# Addon-mapleCUx_OneWire-RS485-003.net
KiCad netlist of a schematic drawn in EAGLE
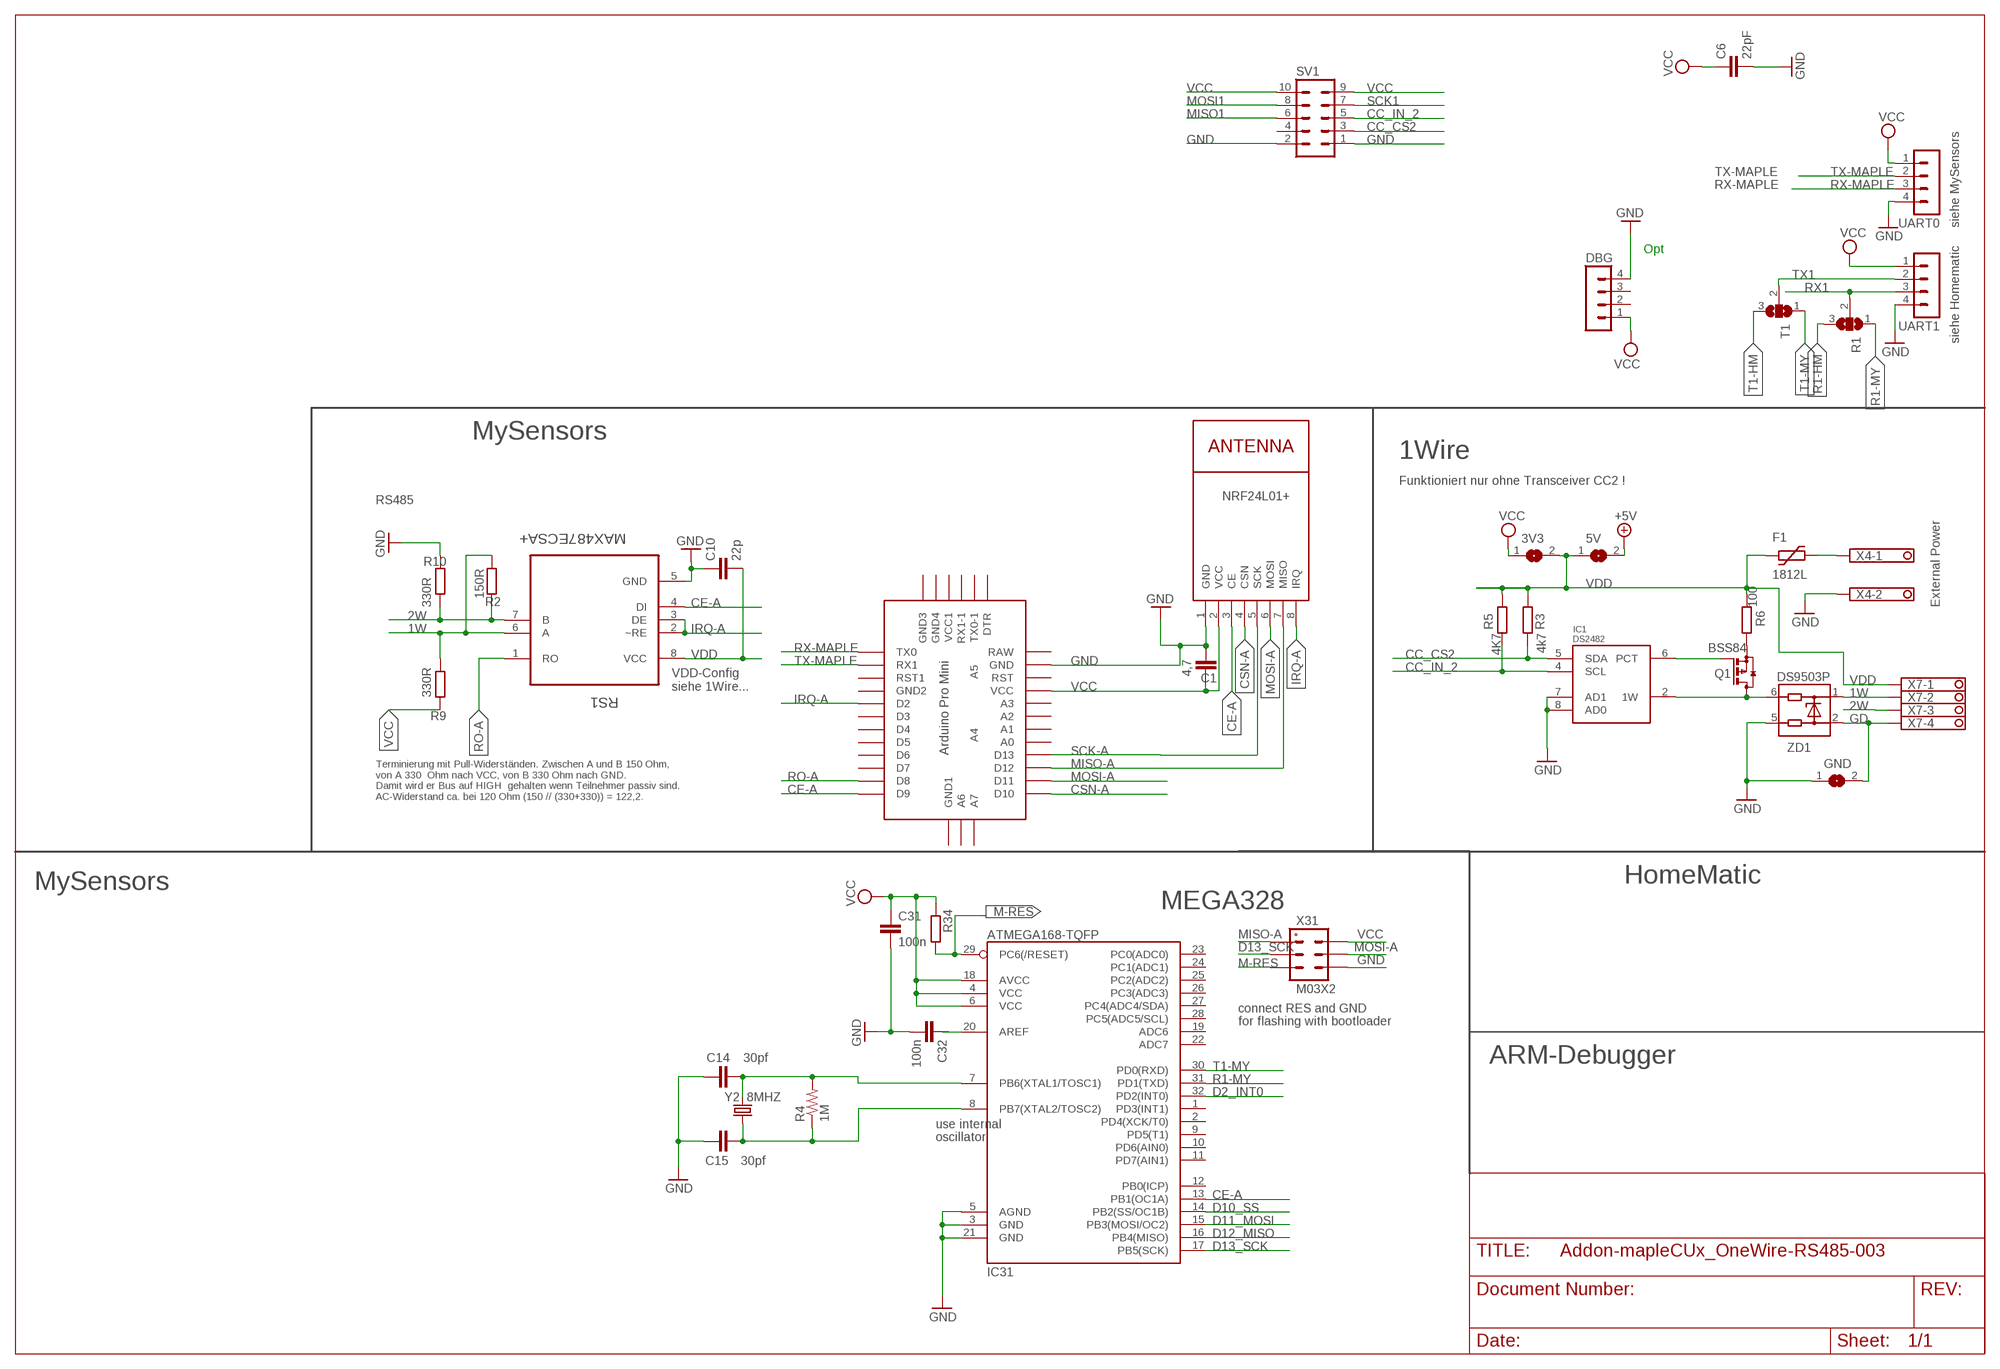
[diagram p0: schematic, sheet 1]

(export (version "E")
  (design (tool "Eeschema 10.0.6"))
  (components
    (comp (ref "3V3") (value "SJ") (footprint "eagle-import:SJ") (libsource (lib "eagle-import") (part "SJ")))
    (comp (ref "5V") (value "SJ") (footprint "eagle-import:SJ") (libsource (lib "eagle-import") (part "SJ")))
    (comp (ref "C1")
      (value "4,7")
      (footprint "eagle-import:C1210")
      (libsource (lib "eagle-import") (part "C-EUC1210"))
    )
    (comp (ref "C6")
      (value "22pF")
      (footprint "eagle-import:C0805")
      (libsource (lib "eagle-import") (part "C-EUC0805"))
    )
    (comp (ref "C10")
      (value "22p")
      (footprint "eagle-import:C0805")
      (libsource (lib "eagle-import") (part "C-EUC0805"))
    )
    (comp (ref "C14")
      (value "30pf")
      (footprint "eagle-import:0805")
      (libsource (lib "eagle-import") (part "CAP0805"))
    )
    (comp (ref "C15")
      (value "30pf")
      (footprint "eagle-import:0805")
      (libsource (lib "eagle-import") (part "CAP0805"))
    )
    (comp (ref "C31")
      (value "100n")
      (footprint "eagle-import:C0805")
      (libsource (lib "eagle-import") (part "C-EUC0805"))
    )
    (comp (ref "C32")
      (value "100n")
      (footprint "eagle-import:C0805")
      (libsource (lib "eagle-import") (part "C-EUC0805"))
    )
    (comp (ref "DBG")
      (value "MA04-1")
      (footprint "eagle-import:MA04-1")
      (libsource (lib "eagle-import") (part "MA04-1"))
    )
    (comp (ref "F1")
      (value "1812L")
      (footprint "eagle-import:1812L")
      (libsource (lib "eagle-import") (part "1812L"))
    )
    (comp (ref "GND") (value "SJ") (footprint "eagle-import:SJ") (libsource (lib "eagle-import") (part "SJ")))
    (comp (ref "IC1")
      (value "DS2482")
      (footprint "eagle-import:SO08")
      (libsource (lib "eagle-import") (part "DS2482-100S"))
    )
    (comp (ref "IC31")
      (value "ATMEGA168-TQFP")
      (footprint "eagle-import:TQFP32-08")
      (libsource (lib "eagle-import") (part "ATMEGA168-TQFP"))
    )
    (comp (ref "NRF24L01+")
      (value "NRF24L01+")
      (footprint "eagle-import:WIRELESS-NRF24L01")
      (libsource (lib "eagle-import") (part "WIRELESS-NRF24L01"))
    )
    (comp (ref "Q1")
      (value "BSS84")
      (footprint "eagle-import:SOT23")
      (libsource (lib "eagle-import") (part "BSS84"))
    )
    (comp (ref "R1")
      (value "SJ2W")
      (footprint "eagle-import:SJ_2")
      (libsource (lib "eagle-import") (part "SJ2W"))
    )
    (comp (ref "R2")
      (value "150R")
      (footprint "eagle-import:R0805")
      (libsource (lib "eagle-import") (part "R-EU_R0805"))
    )
    (comp (ref "R3")
      (value "4k7")
      (footprint "eagle-import:R0805")
      (libsource (lib "eagle-import") (part "R-EU_R0805"))
    )
    (comp (ref "R4")
      (value "1M")
      (footprint "eagle-import:0805")
      (libsource (lib "eagle-import") (part "RESISTOR0805-RES"))
    )
    (comp (ref "R5")
      (value "4K7")
      (footprint "eagle-import:R0805")
      (libsource (lib "eagle-import") (part "R-EU_R0805"))
    )
    (comp (ref "R6")
      (value "100")
      (footprint "eagle-import:R0805")
      (libsource (lib "eagle-import") (part "R-EU_R0805"))
    )
    (comp (ref "R9")
      (value "330R")
      (footprint "eagle-import:R0805")
      (libsource (lib "eagle-import") (part "R-EU_R0805"))
    )
    (comp (ref "R10")
      (value "330R")
      (footprint "eagle-import:R0805")
      (libsource (lib "eagle-import") (part "R-EU_R0805"))
    )
    (comp (ref "R34")
      (value "R-EU_R0805")
      (footprint "eagle-import:R0805")
      (libsource (lib "eagle-import") (part "R-EU_R0805"))
    )
    (comp (ref "RS1")
      (value "MAX487ECSA+")
      (footprint "eagle-import:SOIC127P600X175-8N")
      (libsource (lib "eagle-import") (part "MAX487ECSA+"))
    )
    (comp (ref "SV1")
      (value "MA05-2")
      (footprint "eagle-import:MA05-2")
      (libsource (lib "eagle-import") (part "MA05-2"))
    )
    (comp (ref "T1")
      (value "SJ2W")
      (footprint "eagle-import:SJ_2")
      (libsource (lib "eagle-import") (part "SJ2W"))
    )
    (comp (ref "U$1")
      (value "ABK-PRO-MINI")
      (footprint "eagle-import:ABK-PRO-MINI")
      (libsource (lib "eagle-import") (part "ABK-PRO-MINI"))
    )
    (comp (ref "UART0")
      (value "MA04-1")
      (footprint "eagle-import:MA04-1")
      (libsource (lib "eagle-import") (part "MA04-1"))
    )
    (comp (ref "UART1")
      (value "MA04-1")
      (footprint "eagle-import:MA04-1")
      (libsource (lib "eagle-import") (part "MA04-1"))
    )
    (comp (ref "X4")
      (value "1751248")
      (footprint "eagle-import:1751248")
      (libsource (lib "eagle-import") (part "1751248"))
    )
    (comp (ref "X7")
      (value "1751264")
      (footprint "eagle-import:1751264")
      (libsource (lib "eagle-import") (part "1751264"))
    )
    (comp (ref "X31")
      (value "M03X2")
      (footprint "eagle-import:2X03-1.27MM_SMD")
      (libsource (lib "eagle-import") (part "M03X2"))
    )
    (comp (ref "Y2")
      (value "8MHZ")
      (footprint "eagle-import:CRYSTAL-TXC-7A")
      (libsource (lib "eagle-import") (part "CRYSTALTXC-7A"))
    )
    (comp (ref "ZD1")
      (value "DS9503P")
      (footprint "eagle-import:TSOC6")
      (libsource (lib "eagle-import") (part "DS9503P"))
    )
  )
  (nets
    (net (code "1") (name "+5V") (class "Default")
      (node (ref "5V") (pin "2") (pinfunction "2_2") (pintype "passive"))
    )
    (net (code "2") (name "/1W") (class "Default")
      (node (ref "R2") (pin "1") (pinfunction "1_1") (pintype "passive"))
      (node (ref "R9") (pin "2") (pinfunction "2_2") (pintype "passive"))
      (node (ref "RS1") (pin "6") (pinfunction "A_6") (pintype "bidirectional"))
      (node (ref "X7") (pin "2") (pinfunction "K_2") (pintype "passive"))
      (node (ref "ZD1") (pin "1") (pinfunction "P$1_1") (pintype "passive"))
    )
    (net (code "3") (name "/2W") (class "Default")
      (node (ref "R10") (pin "1") (pinfunction "1_1") (pintype "passive"))
      (node (ref "R2") (pin "2") (pinfunction "2_2") (pintype "passive"))
      (node (ref "RS1") (pin "7") (pinfunction "B_7") (pintype "bidirectional"))
      (node (ref "X7") (pin "3") (pinfunction "K_3") (pintype "passive"))
    )
    (net (code "4") (name "/CC_CS2") (class "Default")
      (node (ref "IC1") (pin "5") (pinfunction "SDA_5") (pintype "bidirectional"))
      (node (ref "R3") (pin "2") (pinfunction "2_2") (pintype "passive"))
      (node (ref "SV1") (pin "3") (pinfunction "3_3") (pintype "passive"))
    )
    (net (code "5") (name "/CC_IN_2") (class "Default")
      (node (ref "IC1") (pin "4") (pinfunction "SCL_4") (pintype "input"))
      (node (ref "R5") (pin "2") (pinfunction "2_2") (pintype "passive"))
      (node (ref "SV1") (pin "5") (pinfunction "5_5") (pintype "passive"))
    )
    (net (code "6") (name "/D2_INT0") (class "Default")
      (node (ref "IC31") (pin "32") (pinfunction "PD2(INT0)_32") (pintype "bidirectional"))
    )
    (net (code "7") (name "/D10_SS") (class "Default")
      (node (ref "IC31") (pin "14") (pinfunction "PB2(SS/OC1B)_14") (pintype "bidirectional"))
    )
    (net (code "8") (name "/D11_MOSI") (class "Default")
      (node (ref "IC31") (pin "15") (pinfunction "PB3(MOSI/OC2)_15") (pintype "bidirectional"))
    )
    (net (code "9") (name "/D12_MISO") (class "Default")
      (node (ref "IC31") (pin "16") (pinfunction "PB4(MISO)_16") (pintype "bidirectional"))
    )
    (net (code "10") (name "/D13_SCK") (class "Default")
      (node (ref "IC31") (pin "17") (pinfunction "PB5(SCK)_17") (pintype "bidirectional"))
      (node (ref "X31") (pin "P$3") (pinfunction "3_P$3") (pintype "passive"))
    )
    (net (code "11") (name "/GD") (class "Default")
      (node (ref "GND") (pin "2") (pinfunction "2_2") (pintype "passive"))
      (node (ref "X7") (pin "4") (pinfunction "K_4") (pintype "passive"))
      (node (ref "ZD1") (pin "2") (pinfunction "P$2_2") (pintype "passive"))
    )
    (net (code "12") (name "/M-RES") (class "Default")
      (node (ref "IC31") (pin "29") (pinfunction "PC6(/RESET)_29") (pintype "bidirectional"))
      (node (ref "R34") (pin "2") (pinfunction "2_2") (pintype "passive"))
      (node (ref "X31") (pin "P$5") (pinfunction "5_P$5") (pintype "passive"))
    )
    (net (code "13") (name "/MISO-A") (class "Default")
      (node (ref "NRF24L01+") (pin "7") (pinfunction "MISO_7") (pintype "bidirectional"))
      (node (ref "U$1") (pin "D12") (pinfunction "D12_D12") (pintype "bidirectional"))
      (node (ref "X31") (pin "P$1") (pinfunction "1_P$1") (pintype "passive"))
    )
    (net (code "14") (name "/MISO1") (class "Default")
      (node (ref "SV1") (pin "6") (pinfunction "6_6") (pintype "passive"))
    )
    (net (code "15") (name "/MOSI1") (class "Default")
      (node (ref "SV1") (pin "8") (pinfunction "8_8") (pintype "passive"))
    )
    (net (code "16") (name "/RX-MAPLE") (class "Default")
      (node (ref "U$1") (pin "TX0") (pinfunction "TX0_TX0") (pintype "bidirectional"))
      (node (ref "UART0") (pin "3") (pinfunction "3_3") (pintype "passive"))
    )
    (net (code "17") (name "/RX1") (class "Default")
      (node (ref "R1") (pin "2") (pinfunction "2_2") (pintype "passive"))
      (node (ref "UART1") (pin "3") (pinfunction "3_3") (pintype "passive"))
    )
    (net (code "18") (name "/SCK-A") (class "Default")
      (node (ref "NRF24L01+") (pin "5") (pinfunction "SCK_5") (pintype "bidirectional"))
      (node (ref "U$1") (pin "D13") (pinfunction "D13_D13") (pintype "bidirectional"))
    )
    (net (code "19") (name "/SCK1") (class "Default")
      (node (ref "SV1") (pin "7") (pinfunction "7_7") (pintype "passive"))
    )
    (net (code "20") (name "/TX-MAPLE") (class "Default")
      (node (ref "U$1") (pin "RX1") (pinfunction "RX1_RX1") (pintype "bidirectional"))
      (node (ref "UART0") (pin "2") (pinfunction "2_2") (pintype "passive"))
    )
    (net (code "21") (name "/TX1") (class "Default")
      (node (ref "T1") (pin "2") (pinfunction "2_2") (pintype "passive"))
      (node (ref "UART1") (pin "2") (pinfunction "2_2") (pintype "passive"))
    )
    (net (code "22") (name "/VDD") (class "Default")
      (node (ref "3V3") (pin "2") (pinfunction "2_2") (pintype "passive"))
      (node (ref "5V") (pin "1") (pinfunction "1_1") (pintype "passive"))
      (node (ref "C10") (pin "2") (pinfunction "2_2") (pintype "passive"))
      (node (ref "F1") (pin "P$1") (pinfunction "1_P$1") (pintype "passive"))
      (node (ref "R3") (pin "1") (pinfunction "1_1") (pintype "passive"))
      (node (ref "R5") (pin "1") (pinfunction "1_1") (pintype "passive"))
      (node (ref "R6") (pin "2") (pinfunction "2_2") (pintype "passive"))
      (node (ref "RS1") (pin "8") (pinfunction "VCC_8") (pintype "power_in"))
      (node (ref "X7") (pin "1") (pinfunction "K_1") (pintype "passive"))
    )
    (net (code "23") (name "CE-A") (class "Default")
      (node (ref "IC31") (pin "13") (pinfunction "PB1(OC1A)_13") (pintype "bidirectional"))
      (node (ref "NRF24L01+") (pin "3") (pinfunction "CE_3") (pintype "bidirectional"))
      (node (ref "RS1") (pin "4") (pinfunction "DI_4") (pintype "input"))
      (node (ref "U$1") (pin "D9") (pinfunction "D9_D9") (pintype "bidirectional"))
    )
    (net (code "24") (name "CSN-A") (class "Default")
      (node (ref "NRF24L01+") (pin "4") (pinfunction "CSN_4") (pintype "bidirectional"))
      (node (ref "U$1") (pin "D10") (pinfunction "D10_D10") (pintype "bidirectional"))
    )
    (net (code "25") (name "GND") (class "Default")
      (node (ref "C1") (pin "1") (pinfunction "1_1") (pintype "passive"))
      (node (ref "C10") (pin "1") (pinfunction "1_1") (pintype "passive"))
      (node (ref "C14") (pin "1") (pinfunction "1_1") (pintype "passive"))
      (node (ref "C15") (pin "1") (pinfunction "1_1") (pintype "passive"))
      (node (ref "C31") (pin "2") (pinfunction "2_2") (pintype "passive"))
      (node (ref "C32") (pin "2") (pinfunction "2_2") (pintype "passive"))
      (node (ref "C6") (pin "2") (pinfunction "2_2") (pintype "passive"))
      (node (ref "DBG") (pin "4") (pinfunction "4_4") (pintype "passive"))
      (node (ref "GND") (pin "1") (pinfunction "1_1") (pintype "passive"))
      (node (ref "IC1") (pin "7") (pinfunction "AD1_7") (pintype "input"))
      (node (ref "IC1") (pin "8") (pinfunction "AD0_8") (pintype "input"))
      (node (ref "IC31") (pin "21") (pinfunction "GND_21") (pintype "bidirectional"))
      (node (ref "IC31") (pin "3") (pinfunction "GND_3") (pintype "bidirectional"))
      (node (ref "IC31") (pin "5") (pinfunction "AGND_5") (pintype "bidirectional"))
      (node (ref "NRF24L01+") (pin "1") (pinfunction "GND_1") (pintype "power_in"))
      (node (ref "R10") (pin "2") (pinfunction "2_2") (pintype "passive"))
      (node (ref "RS1") (pin "5") (pinfunction "GND_5") (pintype "passive"))
      (node (ref "SV1") (pin "1") (pinfunction "1_1") (pintype "passive"))
      (node (ref "SV1") (pin "2") (pinfunction "2_2") (pintype "passive"))
      (node (ref "U$1") (pin "GND") (pinfunction "GND_GND") (pintype "bidirectional"))
      (node (ref "UART0") (pin "4") (pinfunction "4_4") (pintype "passive"))
      (node (ref "UART1") (pin "4") (pinfunction "4_4") (pintype "passive"))
      (node (ref "X31") (pin "P$6") (pinfunction "6_P$6") (pintype "passive"))
      (node (ref "X4") (pin "2") (pinfunction "K_2") (pintype "passive"))
      (node (ref "ZD1") (pin "5") (pinfunction "P$3_5") (pintype "passive"))
    )
    (net (code "26") (name "IRQ-A") (class "Default")
      (node (ref "NRF24L01+") (pin "8") (pinfunction "IRQ_8") (pintype "bidirectional"))
      (node (ref "RS1") (pin "2") (pinfunction "~{RE}_2") (pintype "input"))
      (node (ref "RS1") (pin "3") (pinfunction "DE_3") (pintype "input"))
      (node (ref "U$1") (pin "D2") (pinfunction "D2_D2") (pintype "bidirectional"))
    )
    (net (code "27") (name "MOSI-A") (class "Default")
      (node (ref "NRF24L01+") (pin "6") (pinfunction "MOSI_6") (pintype "bidirectional"))
      (node (ref "U$1") (pin "D11") (pinfunction "D11_D11") (pintype "bidirectional"))
      (node (ref "X31") (pin "P$4") (pinfunction "4_P$4") (pintype "passive"))
    )
    (net (code "28") (name "Net-(F1-2)") (class "Default")
      (node (ref "F1") (pin "P$2") (pinfunction "2_P$2") (pintype "passive"))
      (node (ref "X4") (pin "1") (pinfunction "K_1") (pintype "passive"))
    )
    (net (code "29") (name "Net-(IC1A-1W)") (class "Default")
      (node (ref "IC1") (pin "2") (pinfunction "1W_2") (pintype "open_collector"))
      (node (ref "Q1") (pin "3") (pinfunction "D_3") (pintype "passive"))
      (node (ref "ZD1") (pin "6") (pinfunction "P$4_6") (pintype "passive"))
    )
    (net (code "30") (name "Net-(IC1A-PCT)") (class "Default")
      (node (ref "IC1") (pin "6") (pinfunction "PCT_6") (pintype "output"))
      (node (ref "Q1") (pin "1") (pinfunction "G_1") (pintype "passive"))
    )
    (net (code "31") (name "Net-(IC31-AREF)") (class "Default")
      (node (ref "C32") (pin "1") (pinfunction "1_1") (pintype "passive"))
      (node (ref "IC31") (pin "20") (pinfunction "AREF_20") (pintype "bidirectional"))
    )
    (net (code "32") (name "Net-(IC31-PB6(XTAL1{slash}TOSC1))") (class "Default")
      (node (ref "C14") (pin "2") (pinfunction "2_2") (pintype "passive"))
      (node (ref "IC31") (pin "7") (pinfunction "PB6(XTAL1/TOSC1)_7") (pintype "bidirectional"))
      (node (ref "R4") (pin "2") (pinfunction "2_2") (pintype "passive"))
      (node (ref "Y2") (pin "P$2") (pinfunction "2_P$2") (pintype "passive"))
    )
    (net (code "33") (name "Net-(IC31-PB7(XTAL2{slash}TOSC2))") (class "Default")
      (node (ref "C15") (pin "2") (pinfunction "2_2") (pintype "passive"))
      (node (ref "IC31") (pin "8") (pinfunction "PB7(XTAL2/TOSC2)_8") (pintype "bidirectional"))
      (node (ref "R4") (pin "1") (pinfunction "1_1") (pintype "passive"))
      (node (ref "Y2") (pin "P$1") (pinfunction "1_P$1") (pintype "passive"))
    )
    (net (code "34") (name "Net-(Q1-S)") (class "Default")
      (node (ref "Q1") (pin "2") (pinfunction "S_2") (pintype "passive"))
      (node (ref "R6") (pin "1") (pinfunction "1_1") (pintype "passive"))
    )
    (net (code "35") (name "R1-HM") (class "Default")
      (node (ref "R1") (pin "3") (pinfunction "3_3") (pintype "passive"))
    )
    (net (code "36") (name "R1-MY") (class "Default")
      (node (ref "IC31") (pin "31") (pinfunction "PD1(TXD)_31") (pintype "bidirectional"))
      (node (ref "R1") (pin "1") (pinfunction "1_1") (pintype "passive"))
    )
    (net (code "37") (name "RO-A") (class "Default")
      (node (ref "RS1") (pin "1") (pinfunction "RO_1") (pintype "output"))
      (node (ref "U$1") (pin "D8") (pinfunction "D8_D8") (pintype "bidirectional"))
    )
    (net (code "38") (name "T1-HM") (class "Default")
      (node (ref "T1") (pin "3") (pinfunction "3_3") (pintype "passive"))
    )
    (net (code "39") (name "T1-MY") (class "Default")
      (node (ref "IC31") (pin "30") (pinfunction "PD0(RXD)_30") (pintype "bidirectional"))
      (node (ref "T1") (pin "1") (pinfunction "1_1") (pintype "passive"))
    )
    (net (code "40") (name "VCC") (class "Default")
      (node (ref "3V3") (pin "1") (pinfunction "1_1") (pintype "passive"))
      (node (ref "C1") (pin "2") (pinfunction "2_2") (pintype "passive"))
      (node (ref "C31") (pin "1") (pinfunction "1_1") (pintype "passive"))
      (node (ref "C6") (pin "1") (pinfunction "1_1") (pintype "passive"))
      (node (ref "DBG") (pin "1") (pinfunction "1_1") (pintype "passive"))
      (node (ref "IC31") (pin "18") (pinfunction "AVCC_18") (pintype "bidirectional"))
      (node (ref "IC31") (pin "4") (pinfunction "VCC_4") (pintype "bidirectional"))
      (node (ref "IC31") (pin "6") (pinfunction "VCC_6") (pintype "bidirectional"))
      (node (ref "NRF24L01+") (pin "2") (pinfunction "VCC_2") (pintype "power_in"))
      (node (ref "R34") (pin "1") (pinfunction "1_1") (pintype "passive"))
      (node (ref "R9") (pin "1") (pinfunction "1_1") (pintype "passive"))
      (node (ref "SV1") (pin "10") (pinfunction "10_10") (pintype "passive"))
      (node (ref "SV1") (pin "9") (pinfunction "9_9") (pintype "passive"))
      (node (ref "U$1") (pin "VCC") (pinfunction "VCC_VCC") (pintype "bidirectional"))
      (node (ref "UART0") (pin "1") (pinfunction "1_1") (pintype "passive"))
      (node (ref "UART1") (pin "1") (pinfunction "1_1") (pintype "passive"))
      (node (ref "X31") (pin "P$2") (pinfunction "2_P$2") (pintype "passive"))
    )
    (net (code "41") (name "unconnected-(DBG-Pad2)") (class "Default")
      (node (ref "DBG") (pin "2") (pinfunction "2_2") (pintype "passive"))
    )
    (net (code "42") (name "unconnected-(DBG-Pad3)") (class "Default")
      (node (ref "DBG") (pin "3") (pinfunction "3_3") (pintype "passive"))
    )
    (net (code "43") (name "unconnected-(IC31-ADC6-Pad19)") (class "Default")
      (node (ref "IC31") (pin "19") (pinfunction "ADC6_19") (pintype "bidirectional"))
    )
    (net (code "44") (name "unconnected-(IC31-ADC7-Pad22)") (class "Default")
      (node (ref "IC31") (pin "22") (pinfunction "ADC7_22") (pintype "bidirectional"))
    )
    (net (code "45") (name "unconnected-(IC31-PB0(ICP)-Pad12)") (class "Default")
      (node (ref "IC31") (pin "12") (pinfunction "PB0(ICP)_12") (pintype "bidirectional"))
    )
    (net (code "46") (name "unconnected-(IC31-PC0(ADC0)-Pad23)") (class "Default")
      (node (ref "IC31") (pin "23") (pinfunction "PC0(ADC0)_23") (pintype "bidirectional"))
    )
    (net (code "47") (name "unconnected-(IC31-PC1(ADC1)-Pad24)") (class "Default")
      (node (ref "IC31") (pin "24") (pinfunction "PC1(ADC1)_24") (pintype "bidirectional"))
    )
    (net (code "48") (name "unconnected-(IC31-PC2(ADC2)-Pad25)") (class "Default")
      (node (ref "IC31") (pin "25") (pinfunction "PC2(ADC2)_25") (pintype "bidirectional"))
    )
    (net (code "49") (name "unconnected-(IC31-PC3(ADC3)-Pad26)") (class "Default")
      (node (ref "IC31") (pin "26") (pinfunction "PC3(ADC3)_26") (pintype "bidirectional"))
    )
    (net (code "50") (name "unconnected-(IC31-PC4(ADC4{slash}SDA)-Pad27)") (class "Default")
      (node (ref "IC31") (pin "27") (pinfunction "PC4(ADC4/SDA)_27") (pintype "bidirectional"))
    )
    (net (code "51") (name "unconnected-(IC31-PC5(ADC5{slash}SCL)-Pad28)") (class "Default")
      (node (ref "IC31") (pin "28") (pinfunction "PC5(ADC5/SCL)_28") (pintype "bidirectional"))
    )
    (net (code "52") (name "unconnected-(IC31-PD3(INT1)-Pad1)") (class "Default")
      (node (ref "IC31") (pin "1") (pinfunction "PD3(INT1)_1") (pintype "bidirectional"))
    )
    (net (code "53") (name "unconnected-(IC31-PD4(XCK{slash}T0)-Pad2)") (class "Default")
      (node (ref "IC31") (pin "2") (pinfunction "PD4(XCK/T0)_2") (pintype "bidirectional"))
    )
    (net (code "54") (name "unconnected-(IC31-PD5(T1)-Pad9)") (class "Default")
      (node (ref "IC31") (pin "9") (pinfunction "PD5(T1)_9") (pintype "bidirectional"))
    )
    (net (code "55") (name "unconnected-(IC31-PD6(AIN0)-Pad10)") (class "Default")
      (node (ref "IC31") (pin "10") (pinfunction "PD6(AIN0)_10") (pintype "bidirectional"))
    )
    (net (code "56") (name "unconnected-(IC31-PD7(AIN1)-Pad11)") (class "Default")
      (node (ref "IC31") (pin "11") (pinfunction "PD7(AIN1)_11") (pintype "bidirectional"))
    )
    (net (code "57") (name "unconnected-(SV1-Pad4)") (class "Default")
      (node (ref "SV1") (pin "4") (pinfunction "4_4") (pintype "passive"))
    )
    (net (code "58") (name "unconnected-(U$1-GND1-PadGND4)") (class "Default")
      (node (ref "U$1") (pin "GND4") (pinfunction "GND1_GND4") (pintype "bidirectional"))
    )
    (net (code "59") (name "unconnected-(U$1-GND2-PadGND1)") (class "Default")
      (node (ref "U$1") (pin "GND1") (pinfunction "GND2_GND1") (pintype "bidirectional"))
    )
    (net (code "60") (name "unconnected-(U$1-GND3-PadGND2)") (class "Default")
      (node (ref "U$1") (pin "GND2") (pinfunction "GND3_GND2") (pintype "bidirectional"))
    )
    (net (code "61") (name "unconnected-(U$1-GND4-PadGND3)") (class "Default")
      (node (ref "U$1") (pin "GND3") (pinfunction "GND4_GND3") (pintype "bidirectional"))
    )
    (net (code "62") (name "unconnected-(U$1-PadA0)") (class "Default")
      (node (ref "U$1") (pin "A0") (pinfunction "A0_A0") (pintype "bidirectional"))
    )
    (net (code "63") (name "unconnected-(U$1-PadA1)") (class "Default")
      (node (ref "U$1") (pin "A1") (pinfunction "A1_A1") (pintype "bidirectional"))
    )
    (net (code "64") (name "unconnected-(U$1-PadA2)") (class "Default")
      (node (ref "U$1") (pin "A2") (pinfunction "A2_A2") (pintype "bidirectional"))
    )
    (net (code "65") (name "unconnected-(U$1-PadA3)") (class "Default")
      (node (ref "U$1") (pin "A3") (pinfunction "A3_A3") (pintype "bidirectional"))
    )
    (net (code "66") (name "unconnected-(U$1-PadA4)") (class "Default")
      (node (ref "U$1") (pin "A4") (pinfunction "A4_A4") (pintype "bidirectional"))
    )
    (net (code "67") (name "unconnected-(U$1-PadA5)") (class "Default")
      (node (ref "U$1") (pin "A5") (pinfunction "A5_A5") (pintype "bidirectional"))
    )
    (net (code "68") (name "unconnected-(U$1-PadA6)") (class "Default")
      (node (ref "U$1") (pin "A6") (pinfunction "A6_A6") (pintype "bidirectional"))
    )
    (net (code "69") (name "unconnected-(U$1-PadA7)") (class "Default")
      (node (ref "U$1") (pin "A7") (pinfunction "A7_A7") (pintype "bidirectional"))
    )
    (net (code "70") (name "unconnected-(U$1-PadD3)") (class "Default")
      (node (ref "U$1") (pin "D3") (pinfunction "D3_D3") (pintype "bidirectional"))
    )
    (net (code "71") (name "unconnected-(U$1-PadD4)") (class "Default")
      (node (ref "U$1") (pin "D4") (pinfunction "D4_D4") (pintype "bidirectional"))
    )
    (net (code "72") (name "unconnected-(U$1-PadD5)") (class "Default")
      (node (ref "U$1") (pin "D5") (pinfunction "D5_D5") (pintype "bidirectional"))
    )
    (net (code "73") (name "unconnected-(U$1-PadD6)") (class "Default")
      (node (ref "U$1") (pin "D6") (pinfunction "D6_D6") (pintype "bidirectional"))
    )
    (net (code "74") (name "unconnected-(U$1-PadD7)") (class "Default")
      (node (ref "U$1") (pin "D7") (pinfunction "D7_D7") (pintype "bidirectional"))
    )
    (net (code "75") (name "unconnected-(U$1-PadDTR)") (class "Default")
      (node (ref "U$1") (pin "DTR") (pinfunction "DTR_DTR") (pintype "bidirectional"))
    )
    (net (code "76") (name "unconnected-(U$1-PadRAW)") (class "Default")
      (node (ref "U$1") (pin "RAW") (pinfunction "RAW_RAW") (pintype "bidirectional"))
    )
    (net (code "77") (name "unconnected-(U$1-PadRST)") (class "Default")
      (node (ref "U$1") (pin "RST") (pinfunction "RST_RST") (pintype "bidirectional"))
    )
    (net (code "78") (name "unconnected-(U$1-PadRST1)") (class "Default")
      (node (ref "U$1") (pin "RST1") (pinfunction "RST1_RST1") (pintype "bidirectional"))
    )
    (net (code "79") (name "unconnected-(U$1-PadRX1-1)") (class "Default")
      (node (ref "U$1") (pin "RX1-1") (pinfunction "RX1-1_RX1-1") (pintype "bidirectional"))
    )
    (net (code "80") (name "unconnected-(U$1-PadTX0-1)") (class "Default")
      (node (ref "U$1") (pin "TX0-1") (pinfunction "TX0-1_TX0-1") (pintype "bidirectional"))
    )
    (net (code "81") (name "unconnected-(U$1-PadVCC1)") (class "Default")
      (node (ref "U$1") (pin "VCC1") (pinfunction "VCC1_VCC1") (pintype "bidirectional"))
    )
  )
)
